# TempSensor.net
KiCad netlist of a schematic drawn in Altium Designer
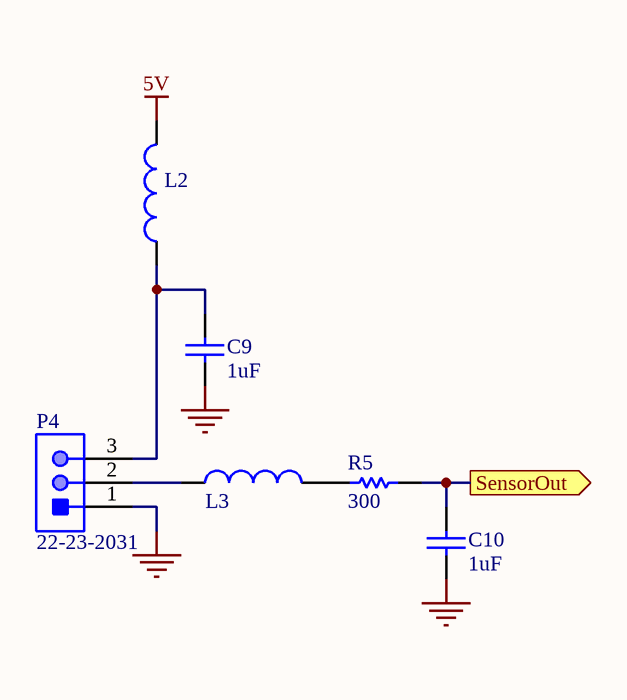
[diagram p0: TempSensor.SchDoc]

(export (version "E")
  (design (tool "Eeschema 10.0.6"))
  (components
    (comp (ref "C9")
      (value "1uF")
      (footprint "CAPC0805(2012)145_N")
      (fields (field (name "TOLERANCE") "Â±20%"))
      (libsource (lib "Altium Content Vault") (part "CAP"))
    )
    (comp (ref "C10")
      (value "1uF")
      (footprint "CAPC0805(2012)145_N")
      (fields (field (name "TOLERANCE") "Â±20%"))
      (libsource (lib "Altium Content Vault") (part "CAP"))
    )
    (comp (ref "L2")
      (value "FBMJ2125HM210NT")
      (footprint "INDC2013X105X50LL20T30")
      (description "Chip Inductor, 21 Ohm, +/- 30%, 6 A, -40 to 125 degC, 0805 (2012 Metric), RoHS, Tape and Reel")
      (fields (field (name "TOLERANCE") "30%"))
      (libsource (lib "Altium Content Vault") (part "IND-2"))
    )
    (comp (ref "L3")
      (value "FBMJ2125HM210NT")
      (footprint "INDC2013X105X50LL20T30")
      (description "Chip Inductor, 21 Ohm, +/- 30%, 6 A, -40 to 125 degC, 0805 (2012 Metric), RoHS, Tape and Reel")
      (fields (field (name "TOLERANCE") "30%"))
      (libsource (lib "Altium Content Vault") (part "IND-2"))
    )
    (comp (ref "P4")
      (value "22-23-2031")
      (footprint "MOLX-22-23-2031_V")
      (description "Male Header, Pitch 2.54 mm, 1 x 3 Position, Height 8.18 mm, Tail Length 3.56 mm, RoHS, Bulk")
      (fields (field (name "MANUFACTURER") "Molex"))
      (libsource (lib "Altium Content Vault") (part "CN-1P-M-R3"))
    )
    (comp (ref "R5")
      (value "300")
      (footprint "RESC0805(2012)_M")
      (description "300R 0.125W 1% 0805 (2012 Metric)  SMD")
      (fields (field (name "TOLERANCE") "1 %") (field (name "POWER") "0.125 W"))
      (libsource (lib "Altium Content Vault") (part "RES"))
    )
  )
  (nets
    (net (code "1") (name "/SensorOut") (class "Default")
      (node (ref "C10") (pin "2") (pinfunction "2_2") (pintype "passive"))
      (node (ref "R5") (pin "2") (pinfunction "2_2") (pintype "passive"))
    )
    (net (code "2") (name "5V") (class "Default")
      (node (ref "L2") (pin "2") (pinfunction "2_2") (pintype "passive"))
    )
    (net (code "3") (name "GND") (class "Default")
      (node (ref "C10") (pin "1") (pinfunction "1_1") (pintype "passive"))
      (node (ref "C9") (pin "2") (pinfunction "2_2") (pintype "passive"))
      (node (ref "P4") (pin "1") (pinfunction "1_1") (pintype "passive"))
    )
    (net (code "4") (name "Net-(C9-Pad1)") (class "Default")
      (node (ref "C9") (pin "1") (pinfunction "1_1") (pintype "passive"))
      (node (ref "L2") (pin "1") (pinfunction "1_1") (pintype "passive"))
      (node (ref "P4") (pin "3") (pinfunction "3_3") (pintype "passive"))
    )
    (net (code "5") (name "Net-(L3-Pad1)") (class "Default")
      (node (ref "L3") (pin "1") (pinfunction "1_1") (pintype "passive"))
      (node (ref "P4") (pin "2") (pinfunction "2_2") (pintype "passive"))
    )
    (net (code "6") (name "Net-(L3-Pad2)") (class "Default")
      (node (ref "L3") (pin "2") (pinfunction "2_2") (pintype "passive"))
      (node (ref "R5") (pin "1") (pinfunction "1_1") (pintype "passive"))
    )
  )
)
